# cv02dobes.net
KiCad netlist of a schematic drawn in EAGLE
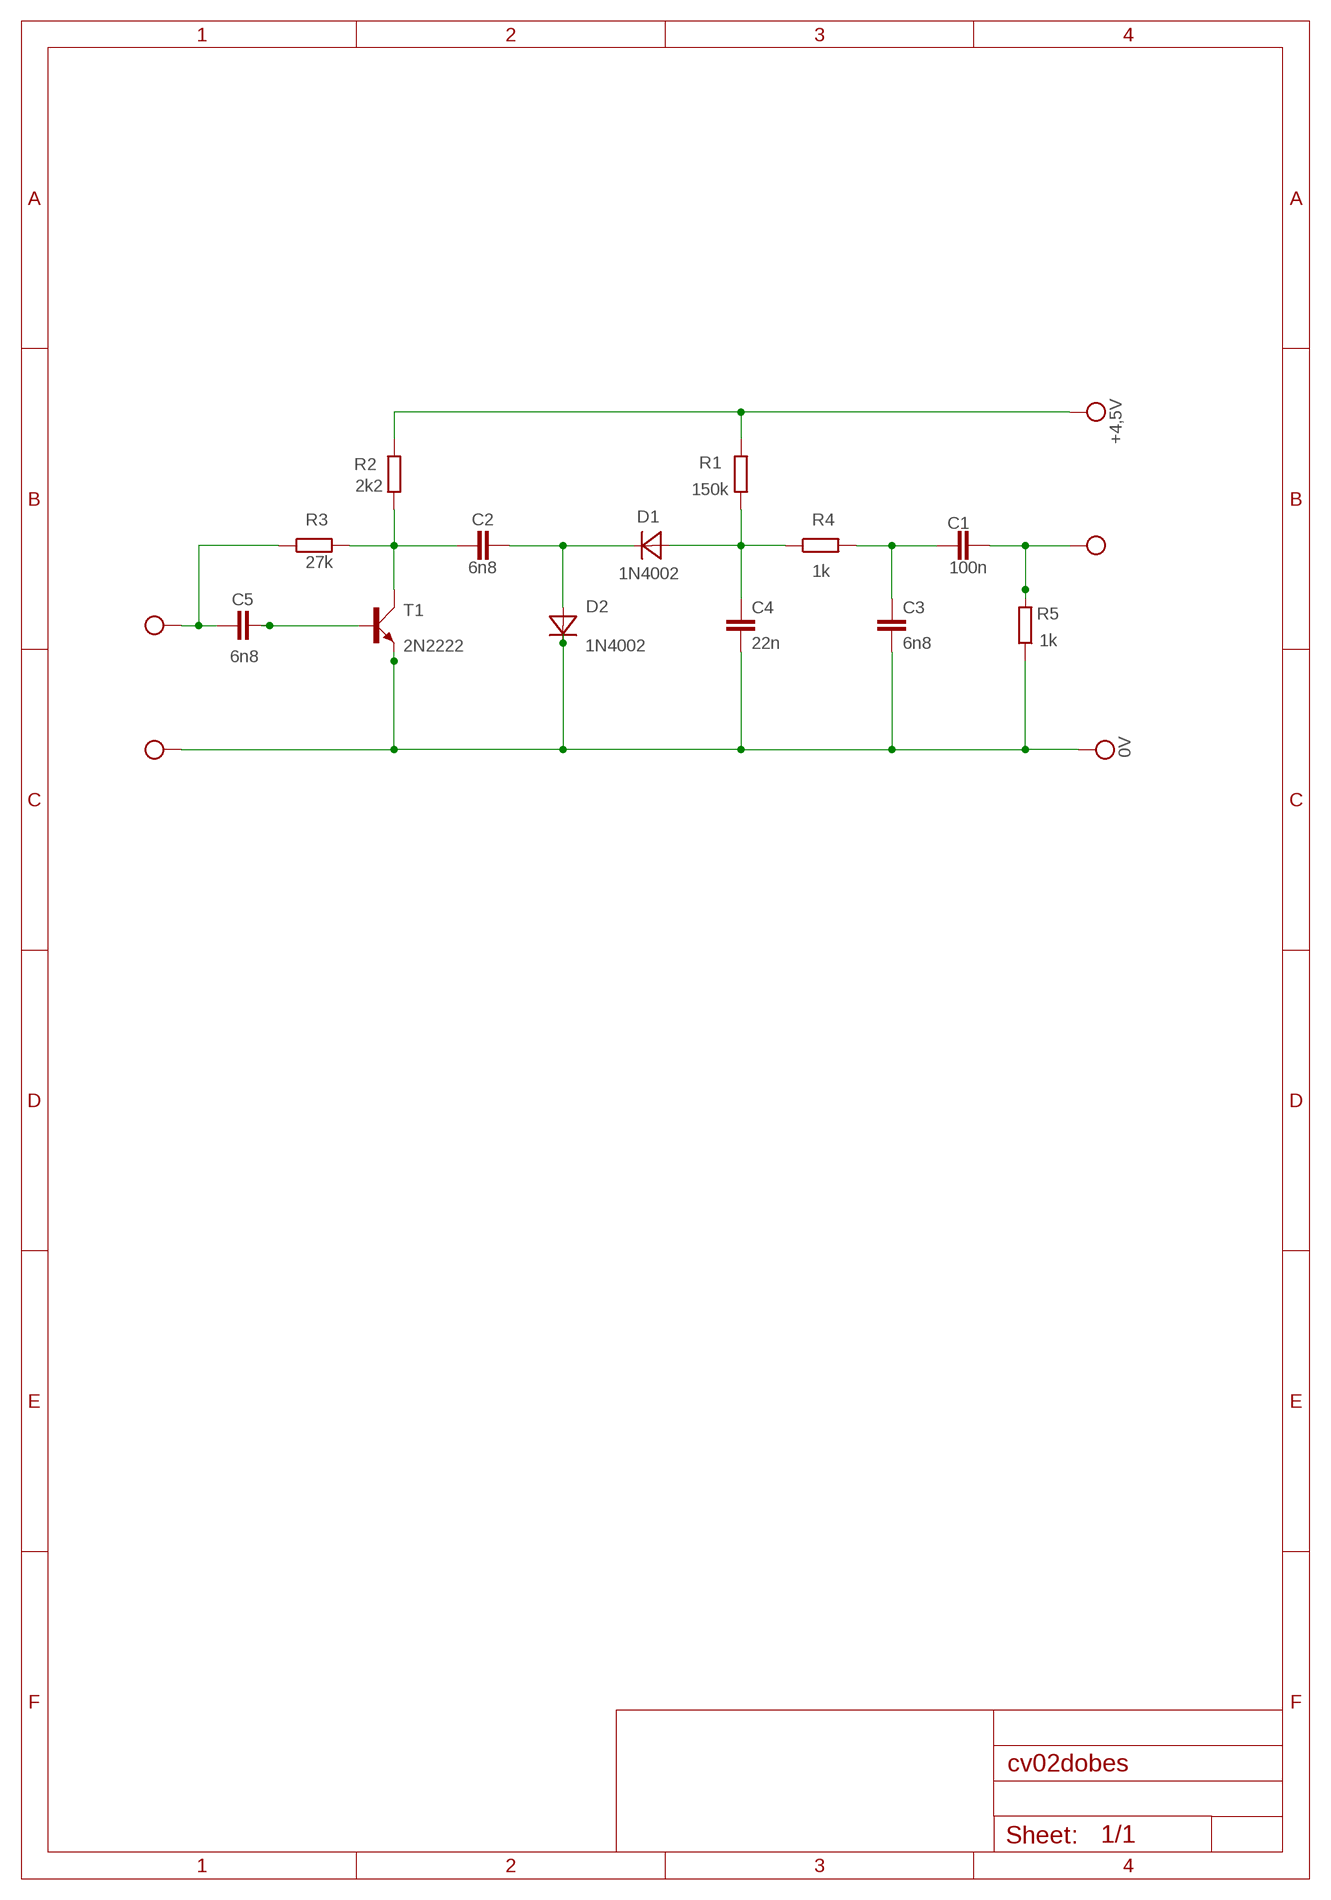
[diagram p0: schematic, sheet 1]

(export (version "E")
  (design (tool "Eeschema 10.0.6"))
  (components
    (comp (ref "C1")
      (value "100n")
      (footprint "eagle-import:HPC0201")
      (libsource (lib "eagle-import") (part "C-EUHPC0201"))
    )
    (comp (ref "C2")
      (value "6n8")
      (footprint "eagle-import:HPC0201")
      (libsource (lib "eagle-import") (part "C-EUHPC0201"))
    )
    (comp (ref "C3")
      (value "6n8")
      (footprint "eagle-import:HPC0201")
      (libsource (lib "eagle-import") (part "C-EUHPC0201"))
    )
    (comp (ref "C4")
      (value "22n")
      (footprint "eagle-import:HPC0201")
      (libsource (lib "eagle-import") (part "C-EUHPC0201"))
    )
    (comp (ref "C5")
      (value "6n8")
      (footprint "eagle-import:HPC0201")
      (libsource (lib "eagle-import") (part "C-EUHPC0201"))
    )
    (comp (ref "D1")
      (value "1N4002")
      (footprint "eagle-import:SMA")
      (libsource (lib "eagle-import") (part "MBRA340T3"))
    )
    (comp (ref "D2")
      (value "1N4002")
      (footprint "eagle-import:SMA")
      (libsource (lib "eagle-import") (part "MBRA340T3"))
    )
    (comp (ref "R1")
      (value "150k")
      (footprint "eagle-import:WSC6927")
      (libsource (lib "eagle-import") (part "R-EU_WSC6927"))
    )
    (comp (ref "R2")
      (value "2k2")
      (footprint "eagle-import:WSC6927")
      (libsource (lib "eagle-import") (part "R-EU_WSC6927"))
    )
    (comp (ref "R3")
      (value "27k")
      (footprint "eagle-import:WSC6927")
      (libsource (lib "eagle-import") (part "R-EU_WSC6927"))
    )
    (comp (ref "R4")
      (value "1k")
      (footprint "eagle-import:WSC6927")
      (libsource (lib "eagle-import") (part "R-EU_WSC6927"))
    )
    (comp (ref "R5")
      (value "1k")
      (footprint "eagle-import:WSC6927")
      (libsource (lib "eagle-import") (part "R-EU_WSC6927"))
    )
    (comp (ref "T1")
      (value "2N2222")
      (footprint "eagle-import:SOT37")
      (libsource (lib "eagle-import") (part "BFR90"))
    )
  )
  (nets
    (net (code "1") (name "+4,5V") (class "Default")
      (node (ref "C1") (pin "2") (pinfunction "2_2") (pintype "passive"))
      (node (ref "C3") (pin "2") (pinfunction "2_2") (pintype "passive"))
      (node (ref "C4") (pin "2") (pinfunction "2_2") (pintype "passive"))
      (node (ref "C5") (pin "1") (pinfunction "1_1") (pintype "passive"))
      (node (ref "D2") (pin "C") (pinfunction "C_C") (pintype "passive"))
      (node (ref "R1") (pin "2") (pinfunction "2_2") (pintype "passive"))
      (node (ref "R2") (pin "2") (pinfunction "2_2") (pintype "passive"))
      (node (ref "R3") (pin "1") (pinfunction "1_1") (pintype "passive"))
      (node (ref "R5") (pin "1") (pinfunction "1_1") (pintype "passive"))
      (node (ref "R5") (pin "2") (pinfunction "2_2") (pintype "passive"))
      (node (ref "T1") (pin "2") (pinfunction "E_2") (pintype "passive"))
    )
    (net (code "2") (name "Net-(C1-Pad1)") (class "Default")
      (node (ref "C1") (pin "1") (pinfunction "1_1") (pintype "passive"))
      (node (ref "C3") (pin "1") (pinfunction "1_1") (pintype "passive"))
      (node (ref "R4") (pin "2") (pinfunction "2_2") (pintype "passive"))
    )
    (net (code "3") (name "Net-(C2-Pad2)") (class "Default")
      (node (ref "C2") (pin "2") (pinfunction "2_2") (pintype "passive"))
      (node (ref "D1") (pin "C") (pinfunction "C_C") (pintype "passive"))
      (node (ref "D2") (pin "A") (pinfunction "A_A") (pintype "passive"))
    )
    (net (code "4") (name "Net-(C4-Pad1)") (class "Default")
      (node (ref "C4") (pin "1") (pinfunction "1_1") (pintype "passive"))
      (node (ref "D1") (pin "A") (pinfunction "A_A") (pintype "passive"))
      (node (ref "R1") (pin "1") (pinfunction "1_1") (pintype "passive"))
      (node (ref "R4") (pin "1") (pinfunction "1_1") (pintype "passive"))
    )
    (net (code "5") (name "Net-(T1-B)") (class "Default")
      (node (ref "C5") (pin "2") (pinfunction "2_2") (pintype "passive"))
      (node (ref "T1") (pin "3") (pinfunction "B_3") (pintype "passive"))
    )
    (net (code "6") (name "Net-(T1-C)") (class "Default")
      (node (ref "C2") (pin "1") (pinfunction "1_1") (pintype "passive"))
      (node (ref "R2") (pin "1") (pinfunction "1_1") (pintype "passive"))
      (node (ref "R3") (pin "2") (pinfunction "2_2") (pintype "passive"))
      (node (ref "T1") (pin "1") (pinfunction "C_1") (pintype "passive"))
    )
  )
)
